# DBoard_Conn.net
KiCad netlist of a schematic drawn in Altium Designer
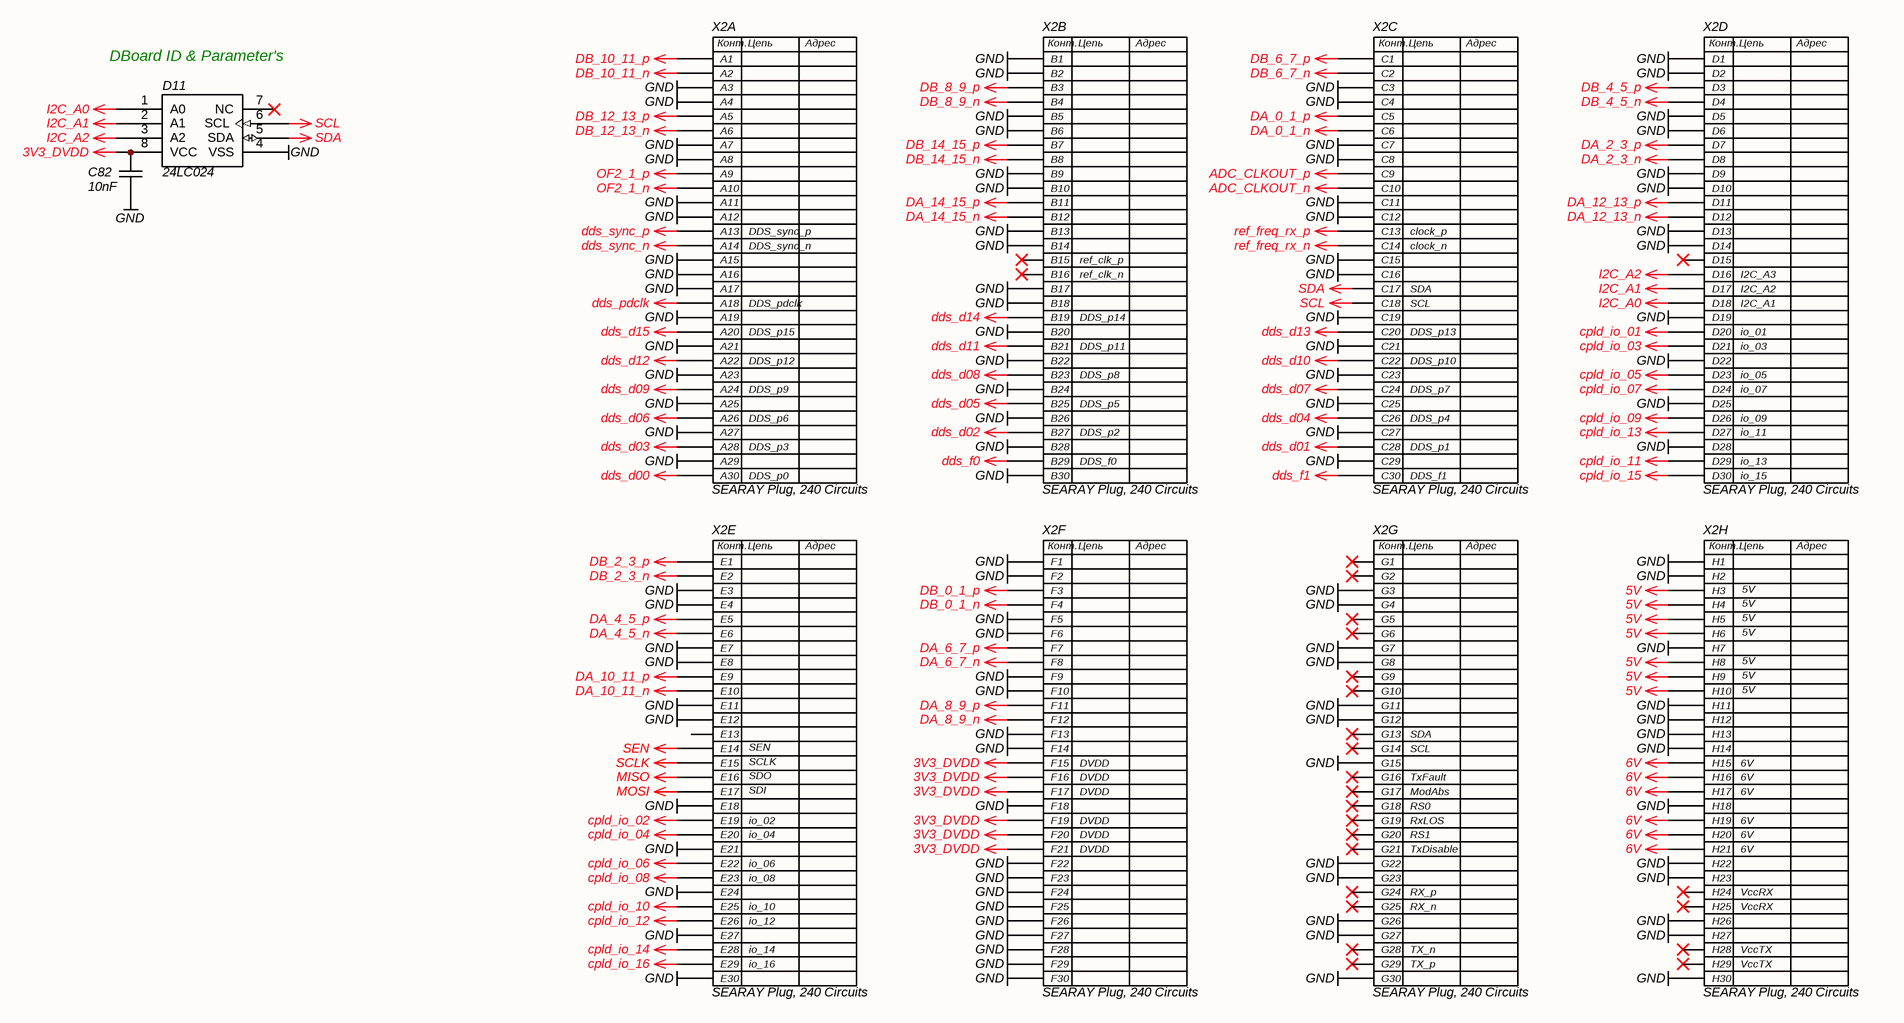
[diagram p0: DBoard_Conn.SchDoc]

(export (version "E")
  (design (tool "Eeschema 10.0.6"))
  (components
    (comp (ref "C82")
      (value "10nF")
      (footprint "C0402")
      (description "SMD Capacitor")
      (fields (field (name "MANUFACTURER") "Murata") (field (name "TOLERANCE") "10%"))
      (libsource (lib "Kintex_SDR") (part "CAP"))
    )
    (comp (ref "D11")
      (value "24LC024")
      (footprint "SOIC_SN8")
      (description "I2C EEPROM")
      (fields (field (name "MANUFACTURER") "Microchip") (field (name "VOLTAGE") "2.5-5.5V"))
      (libsource (lib "Kintex_SDR") (part "24LC024"))
    )
    (comp (ref "X2")
      (value "SEARAY Plug, 240 Circuits")
      (footprint "DBLib:Molex_459703185")
      (description "1.27mm Pitch, SEARAY Plug, 240 Circuits, 2.00mm Unmated Height, 8 Rows, with Pegs")
      (fields (field (name "MANUFACTURER") "Molex"))
      (libsource (lib "") (part "Molex_SEARAY™ 45970_1"))
    )
  )
  (nets
    (net (code "34") (name "3V3_DVDD") (class "Default")
      (node (ref "C82") (pin "2") (pinfunction "2_2") (pintype "passive"))
      (node (ref "D11") (pin "8") (pinfunction "VCC_8") (pintype "power_in"))
      (node (ref "X2") (pin "F15") (pinfunction "F15_F15") (pintype "passive"))
      (node (ref "X2") (pin "F16") (pinfunction "F16_F16") (pintype "passive"))
      (node (ref "X2") (pin "F17") (pinfunction "F17_F17") (pintype "passive"))
      (node (ref "X2") (pin "F19") (pinfunction "F19_F19") (pintype "passive"))
      (node (ref "X2") (pin "F20") (pinfunction "F20_F20") (pintype "passive"))
      (node (ref "X2") (pin "F21") (pinfunction "F21_F21") (pintype "passive"))
    )
    (net (code "35") (name "5V") (class "Default")
      (node (ref "X2") (pin "H10") (pinfunction "H10_H10") (pintype "passive"))
      (node (ref "X2") (pin "H3") (pinfunction "H3_H3") (pintype "passive"))
      (node (ref "X2") (pin "H4") (pinfunction "H4_H4") (pintype "passive"))
      (node (ref "X2") (pin "H5") (pinfunction "H5_H5") (pintype "passive"))
      (node (ref "X2") (pin "H6") (pinfunction "H6_H6") (pintype "passive"))
      (node (ref "X2") (pin "H8") (pinfunction "H8_H8") (pintype "passive"))
      (node (ref "X2") (pin "H9") (pinfunction "H9_H9") (pintype "passive"))
    )
    (net (code "36") (name "6V") (class "Default")
      (node (ref "X2") (pin "H15") (pinfunction "H15_H15") (pintype "passive"))
      (node (ref "X2") (pin "H16") (pinfunction "H16_H16") (pintype "passive"))
      (node (ref "X2") (pin "H17") (pinfunction "H17_H17") (pintype "passive"))
      (node (ref "X2") (pin "H19") (pinfunction "H19_H19") (pintype "passive"))
      (node (ref "X2") (pin "H20") (pinfunction "H20_H20") (pintype "passive"))
      (node (ref "X2") (pin "H21") (pinfunction "H21_H21") (pintype "passive"))
    )
    (net (code "37") (name "ADC_CLKOUT_n") (class "Default")
      (node (ref "X2") (pin "C10") (pinfunction "C10_C10") (pintype "passive"))
    )
    (net (code "38") (name "ADC_CLKOUT_p") (class "Default")
      (node (ref "X2") (pin "C9") (pinfunction "C9_C9") (pintype "passive"))
    )
    (net (code "39") (name "DA_0_1_n") (class "Default")
      (node (ref "X2") (pin "C6") (pinfunction "C6_C6") (pintype "passive"))
    )
    (net (code "40") (name "DA_0_1_p") (class "Default")
      (node (ref "X2") (pin "C5") (pinfunction "C5_C5") (pintype "passive"))
    )
    (net (code "41") (name "DA_2_3_n") (class "Default")
      (node (ref "X2") (pin "D8") (pinfunction "D8_D8") (pintype "passive"))
    )
    (net (code "42") (name "DA_2_3_p") (class "Default")
      (node (ref "X2") (pin "D7") (pinfunction "D7_D7") (pintype "passive"))
    )
    (net (code "43") (name "DA_4_5_n") (class "Default")
      (node (ref "X2") (pin "E6") (pinfunction "E6_E6") (pintype "passive"))
    )
    (net (code "44") (name "DA_4_5_p") (class "Default")
      (node (ref "X2") (pin "E5") (pinfunction "E5_E5") (pintype "passive"))
    )
    (net (code "45") (name "DA_6_7_n") (class "Default")
      (node (ref "X2") (pin "F8") (pinfunction "F8_F8") (pintype "passive"))
    )
    (net (code "46") (name "DA_6_7_p") (class "Default")
      (node (ref "X2") (pin "F7") (pinfunction "F7_F7") (pintype "passive"))
    )
    (net (code "47") (name "DA_8_9_n") (class "Default")
      (node (ref "X2") (pin "F12") (pinfunction "F12_F12") (pintype "passive"))
    )
    (net (code "48") (name "DA_8_9_p") (class "Default")
      (node (ref "X2") (pin "F11") (pinfunction "F11_F11") (pintype "passive"))
    )
    (net (code "49") (name "DA_10_11_n") (class "Default")
      (node (ref "X2") (pin "E10") (pinfunction "E10_E10") (pintype "passive"))
    )
    (net (code "50") (name "DA_10_11_p") (class "Default")
      (node (ref "X2") (pin "E9") (pinfunction "E9_E9") (pintype "passive"))
    )
    (net (code "51") (name "DA_12_13_n") (class "Default")
      (node (ref "X2") (pin "D12") (pinfunction "D12_D12") (pintype "passive"))
    )
    (net (code "52") (name "DA_12_13_p") (class "Default")
      (node (ref "X2") (pin "D11") (pinfunction "D11_D11") (pintype "passive"))
    )
    (net (code "53") (name "DA_14_15_n") (class "Default")
      (node (ref "X2") (pin "B12") (pinfunction "B12_B12") (pintype "passive"))
    )
    (net (code "54") (name "DA_14_15_p") (class "Default")
      (node (ref "X2") (pin "B11") (pinfunction "B11_B11") (pintype "passive"))
    )
    (net (code "55") (name "DB_0_1_n") (class "Default")
      (node (ref "X2") (pin "F4") (pinfunction "F4_F4") (pintype "passive"))
    )
    (net (code "56") (name "DB_0_1_p") (class "Default")
      (node (ref "X2") (pin "F3") (pinfunction "F3_F3") (pintype "passive"))
    )
    (net (code "57") (name "DB_2_3_n") (class "Default")
      (node (ref "X2") (pin "E2") (pinfunction "E2_E2") (pintype "passive"))
    )
    (net (code "58") (name "DB_2_3_p") (class "Default")
      (node (ref "X2") (pin "E1") (pinfunction "E1_E1") (pintype "passive"))
    )
    (net (code "59") (name "DB_4_5_n") (class "Default")
      (node (ref "X2") (pin "D4") (pinfunction "D4_D4") (pintype "passive"))
    )
    (net (code "60") (name "DB_4_5_p") (class "Default")
      (node (ref "X2") (pin "D3") (pinfunction "D3_D3") (pintype "passive"))
    )
    (net (code "61") (name "DB_6_7_n") (class "Default")
      (node (ref "X2") (pin "C2") (pinfunction "C2_C2") (pintype "passive"))
    )
    (net (code "62") (name "DB_6_7_p") (class "Default")
      (node (ref "X2") (pin "C1") (pinfunction "C1_C1") (pintype "passive"))
    )
    (net (code "63") (name "DB_8_9_n") (class "Default")
      (node (ref "X2") (pin "B4") (pinfunction "B4_B4") (pintype "passive"))
    )
    (net (code "64") (name "DB_8_9_p") (class "Default")
      (node (ref "X2") (pin "B3") (pinfunction "B3_B3") (pintype "passive"))
    )
    (net (code "65") (name "DB_10_11_n") (class "Default")
      (node (ref "X2") (pin "A2") (pinfunction "A2_A2") (pintype "passive"))
    )
    (net (code "66") (name "DB_10_11_p") (class "Default")
      (node (ref "X2") (pin "A1") (pinfunction "A1_A1") (pintype "passive"))
    )
    (net (code "67") (name "DB_12_13_n") (class "Default")
      (node (ref "X2") (pin "A6") (pinfunction "A6_A6") (pintype "passive"))
    )
    (net (code "68") (name "DB_12_13_p") (class "Default")
      (node (ref "X2") (pin "A5") (pinfunction "A5_A5") (pintype "passive"))
    )
    (net (code "69") (name "DB_14_15_n") (class "Default")
      (node (ref "X2") (pin "B8") (pinfunction "B8_B8") (pintype "passive"))
    )
    (net (code "70") (name "DB_14_15_p") (class "Default")
      (node (ref "X2") (pin "B7") (pinfunction "B7_B7") (pintype "passive"))
    )
    (net (code "71") (name "GND") (class "Default")
      (node (ref "C82") (pin "1") (pinfunction "1_1") (pintype "passive"))
      (node (ref "D11") (pin "4") (pinfunction "VSS_4") (pintype "power_in"))
      (node (ref "X2") (pin "A11") (pinfunction "A11_A11") (pintype "passive"))
      (node (ref "X2") (pin "A12") (pinfunction "A12_A12") (pintype "passive"))
      (node (ref "X2") (pin "A15") (pinfunction "A15_A15") (pintype "passive"))
      (node (ref "X2") (pin "A16") (pinfunction "A16_A16") (pintype "passive"))
      (node (ref "X2") (pin "A17") (pinfunction "A17_A17") (pintype "passive"))
      (node (ref "X2") (pin "A19") (pinfunction "A19_A19") (pintype "passive"))
      (node (ref "X2") (pin "A21") (pinfunction "A21_A21") (pintype "passive"))
      (node (ref "X2") (pin "A23") (pinfunction "A23_A23") (pintype "passive"))
      (node (ref "X2") (pin "A25") (pinfunction "A25_A25") (pintype "passive"))
      (node (ref "X2") (pin "A27") (pinfunction "A27_A27") (pintype "passive"))
      (node (ref "X2") (pin "A29") (pinfunction "A29_A29") (pintype "passive"))
      (node (ref "X2") (pin "A3") (pinfunction "A3_A3") (pintype "passive"))
      (node (ref "X2") (pin "A4") (pinfunction "A4_A4") (pintype "passive"))
      (node (ref "X2") (pin "A7") (pinfunction "A7_A7") (pintype "passive"))
      (node (ref "X2") (pin "A8") (pinfunction "A8_A8") (pintype "passive"))
      (node (ref "X2") (pin "B1") (pinfunction "B1_B1") (pintype "passive"))
      (node (ref "X2") (pin "B10") (pinfunction "B10_B10") (pintype "passive"))
      (node (ref "X2") (pin "B13") (pinfunction "B13_B13") (pintype "passive"))
      (node (ref "X2") (pin "B14") (pinfunction "B14_B14") (pintype "passive"))
      (node (ref "X2") (pin "B17") (pinfunction "B17_B17") (pintype "passive"))
      (node (ref "X2") (pin "B18") (pinfunction "B18_B18") (pintype "passive"))
      (node (ref "X2") (pin "B2") (pinfunction "B2_B2") (pintype "passive"))
      (node (ref "X2") (pin "B20") (pinfunction "B20_B20") (pintype "passive"))
      (node (ref "X2") (pin "B22") (pinfunction "B22_B22") (pintype "passive"))
      (node (ref "X2") (pin "B24") (pinfunction "B24_B24") (pintype "passive"))
      (node (ref "X2") (pin "B26") (pinfunction "B26_B26") (pintype "passive"))
      (node (ref "X2") (pin "B28") (pinfunction "B28_B28") (pintype "passive"))
      (node (ref "X2") (pin "B30") (pinfunction "B30_B30") (pintype "passive"))
      (node (ref "X2") (pin "B5") (pinfunction "B5_B5") (pintype "passive"))
      (node (ref "X2") (pin "B6") (pinfunction "B6_B6") (pintype "passive"))
      (node (ref "X2") (pin "B9") (pinfunction "B9_B9") (pintype "passive"))
      (node (ref "X2") (pin "C11") (pinfunction "C11_C11") (pintype "passive"))
      (node (ref "X2") (pin "C12") (pinfunction "C12_C12") (pintype "passive"))
      (node (ref "X2") (pin "C15") (pinfunction "C15_C15") (pintype "passive"))
      (node (ref "X2") (pin "C16") (pinfunction "C16_C16") (pintype "passive"))
      (node (ref "X2") (pin "C19") (pinfunction "C19_C19") (pintype "passive"))
      (node (ref "X2") (pin "C21") (pinfunction "C21_C21") (pintype "passive"))
      (node (ref "X2") (pin "C23") (pinfunction "C23_C23") (pintype "passive"))
      (node (ref "X2") (pin "C25") (pinfunction "C25_C25") (pintype "passive"))
      (node (ref "X2") (pin "C27") (pinfunction "C27_C27") (pintype "passive"))
      (node (ref "X2") (pin "C29") (pinfunction "C29_C29") (pintype "passive"))
      (node (ref "X2") (pin "C3") (pinfunction "C3_C3") (pintype "passive"))
      (node (ref "X2") (pin "C4") (pinfunction "C4_C4") (pintype "passive"))
      (node (ref "X2") (pin "C7") (pinfunction "C7_C7") (pintype "passive"))
      (node (ref "X2") (pin "C8") (pinfunction "C8_C8") (pintype "passive"))
      (node (ref "X2") (pin "D1") (pinfunction "D1_D1") (pintype "passive"))
      (node (ref "X2") (pin "D10") (pinfunction "D10_D10") (pintype "passive"))
      (node (ref "X2") (pin "D13") (pinfunction "D13_D13") (pintype "passive"))
      (node (ref "X2") (pin "D14") (pinfunction "D14_D14") (pintype "passive"))
      (node (ref "X2") (pin "D19") (pinfunction "D19_D19") (pintype "passive"))
      (node (ref "X2") (pin "D2") (pinfunction "D2_D2") (pintype "passive"))
      (node (ref "X2") (pin "D22") (pinfunction "D22_D22") (pintype "passive"))
      (node (ref "X2") (pin "D25") (pinfunction "D25_D25") (pintype "passive"))
      (node (ref "X2") (pin "D28") (pinfunction "D28_D28") (pintype "passive"))
      (node (ref "X2") (pin "D5") (pinfunction "D5_D5") (pintype "passive"))
      (node (ref "X2") (pin "D6") (pinfunction "D6_D6") (pintype "passive"))
      (node (ref "X2") (pin "D9") (pinfunction "D9_D9") (pintype "passive"))
      (node (ref "X2") (pin "E11") (pinfunction "E11_E11") (pintype "passive"))
      (node (ref "X2") (pin "E12") (pinfunction "E12_E12") (pintype "passive"))
      (node (ref "X2") (pin "E18") (pinfunction "E18_E18") (pintype "passive"))
      (node (ref "X2") (pin "E21") (pinfunction "E21_E21") (pintype "passive"))
      (node (ref "X2") (pin "E24") (pinfunction "E24_E24") (pintype "passive"))
      (node (ref "X2") (pin "E27") (pinfunction "E27_E27") (pintype "passive"))
      (node (ref "X2") (pin "E3") (pinfunction "E3_E3") (pintype "passive"))
      (node (ref "X2") (pin "E30") (pinfunction "E30_E30") (pintype "passive"))
      (node (ref "X2") (pin "E4") (pinfunction "E4_E4") (pintype "passive"))
      (node (ref "X2") (pin "E7") (pinfunction "E7_E7") (pintype "passive"))
      (node (ref "X2") (pin "E8") (pinfunction "E8_E8") (pintype "passive"))
      (node (ref "X2") (pin "F1") (pinfunction "F1_F1") (pintype "passive"))
      (node (ref "X2") (pin "F10") (pinfunction "F10_F10") (pintype "passive"))
      (node (ref "X2") (pin "F13") (pinfunction "F13_F13") (pintype "passive"))
      (node (ref "X2") (pin "F14") (pinfunction "F14_F14") (pintype "passive"))
      (node (ref "X2") (pin "F18") (pinfunction "F18_F18") (pintype "passive"))
      (node (ref "X2") (pin "F2") (pinfunction "F2_F2") (pintype "passive"))
      (node (ref "X2") (pin "F22") (pinfunction "F22_F22") (pintype "passive"))
      (node (ref "X2") (pin "F23") (pinfunction "F23_F23") (pintype "passive"))
      (node (ref "X2") (pin "F24") (pinfunction "F24_F24") (pintype "passive"))
      (node (ref "X2") (pin "F25") (pinfunction "F25_F25") (pintype "passive"))
      (node (ref "X2") (pin "F26") (pinfunction "F26_F26") (pintype "passive"))
      (node (ref "X2") (pin "F27") (pinfunction "F27_F27") (pintype "passive"))
      (node (ref "X2") (pin "F28") (pinfunction "F28_F28") (pintype "passive"))
      (node (ref "X2") (pin "F29") (pinfunction "F29_F29") (pintype "passive"))
      (node (ref "X2") (pin "F30") (pinfunction "F30_F30") (pintype "passive"))
      (node (ref "X2") (pin "F5") (pinfunction "F5_F5") (pintype "passive"))
      (node (ref "X2") (pin "F6") (pinfunction "F6_F6") (pintype "passive"))
      (node (ref "X2") (pin "F9") (pinfunction "F9_F9") (pintype "passive"))
      (node (ref "X2") (pin "G11") (pinfunction "G11_G11") (pintype "passive"))
      (node (ref "X2") (pin "G12") (pinfunction "G12_G12") (pintype "passive"))
      (node (ref "X2") (pin "G15") (pinfunction "G15_G15") (pintype "passive"))
      (node (ref "X2") (pin "G22") (pinfunction "G22_G22") (pintype "passive"))
      (node (ref "X2") (pin "G23") (pinfunction "G23_G23") (pintype "passive"))
      (node (ref "X2") (pin "G26") (pinfunction "G26_G26") (pintype "passive"))
      (node (ref "X2") (pin "G27") (pinfunction "G27_G27") (pintype "passive"))
      (node (ref "X2") (pin "G3") (pinfunction "G3_G3") (pintype "passive"))
      (node (ref "X2") (pin "G30") (pinfunction "G30_G30") (pintype "passive"))
      (node (ref "X2") (pin "G4") (pinfunction "G4_G4") (pintype "passive"))
      (node (ref "X2") (pin "G7") (pinfunction "G7_G7") (pintype "passive"))
      (node (ref "X2") (pin "G8") (pinfunction "G8_G8") (pintype "passive"))
      (node (ref "X2") (pin "H1") (pinfunction "H1_H1") (pintype "passive"))
      (node (ref "X2") (pin "H11") (pinfunction "H11_H11") (pintype "passive"))
      (node (ref "X2") (pin "H12") (pinfunction "H12_H12") (pintype "passive"))
      (node (ref "X2") (pin "H13") (pinfunction "H13_H13") (pintype "passive"))
      (node (ref "X2") (pin "H14") (pinfunction "H14_H14") (pintype "passive"))
      (node (ref "X2") (pin "H18") (pinfunction "H18_H18") (pintype "passive"))
      (node (ref "X2") (pin "H2") (pinfunction "H2_H2") (pintype "passive"))
      (node (ref "X2") (pin "H22") (pinfunction "H22_H22") (pintype "passive"))
      (node (ref "X2") (pin "H23") (pinfunction "H23_H23") (pintype "passive"))
      (node (ref "X2") (pin "H26") (pinfunction "H26_H26") (pintype "passive"))
      (node (ref "X2") (pin "H27") (pinfunction "H27_H27") (pintype "passive"))
      (node (ref "X2") (pin "H30") (pinfunction "H30_H30") (pintype "passive"))
      (node (ref "X2") (pin "H7") (pinfunction "H7_H7") (pintype "passive"))
    )
    (net (code "72") (name "I2C_A0") (class "Default")
      (node (ref "D11") (pin "1") (pinfunction "A0_1") (pintype "passive"))
      (node (ref "X2") (pin "D18") (pinfunction "D18_D18") (pintype "passive"))
    )
    (net (code "73") (name "I2C_A1") (class "Default")
      (node (ref "D11") (pin "2") (pinfunction "A1_2") (pintype "passive"))
      (node (ref "X2") (pin "D17") (pinfunction "D17_D17") (pintype "passive"))
    )
    (net (code "74") (name "I2C_A2") (class "Default")
      (node (ref "D11") (pin "3") (pinfunction "A2_3") (pintype "passive"))
      (node (ref "X2") (pin "D16") (pinfunction "D16_D16") (pintype "passive"))
    )
    (net (code "75") (name "MISO") (class "Default")
      (node (ref "X2") (pin "E16") (pinfunction "E16_E16") (pintype "passive"))
    )
    (net (code "76") (name "MOSI") (class "Default")
      (node (ref "X2") (pin "E17") (pinfunction "E17_E17") (pintype "passive"))
    )
    (net (code "77") (name "OF2_1_n") (class "Default")
      (node (ref "X2") (pin "A10") (pinfunction "A10_A10") (pintype "passive"))
    )
    (net (code "78") (name "OF2_1_p") (class "Default")
      (node (ref "X2") (pin "A9") (pinfunction "A9_A9") (pintype "passive"))
    )
    (net (code "79") (name "SCL") (class "Default")
      (node (ref "D11") (pin "6") (pinfunction "SCL_6") (pintype "input"))
      (node (ref "X2") (pin "C18") (pinfunction "C18_C18") (pintype "passive"))
    )
    (net (code "80") (name "SCLK") (class "Default")
      (node (ref "X2") (pin "E15") (pinfunction "E15_E15") (pintype "passive"))
    )
    (net (code "81") (name "SDA") (class "Default")
      (node (ref "D11") (pin "5") (pinfunction "SDA_5") (pintype "bidirectional"))
      (node (ref "X2") (pin "C17") (pinfunction "C17_C17") (pintype "passive"))
    )
    (net (code "82") (name "SEN") (class "Default")
      (node (ref "X2") (pin "E14") (pinfunction "E14_E14") (pintype "passive"))
    )
    (net (code "83") (name "cpld_io_01") (class "Default")
      (node (ref "X2") (pin "D20") (pinfunction "D20_D20") (pintype "passive"))
    )
    (net (code "84") (name "cpld_io_02") (class "Default")
      (node (ref "X2") (pin "E19") (pinfunction "E19_E19") (pintype "passive"))
    )
    (net (code "85") (name "cpld_io_03") (class "Default")
      (node (ref "X2") (pin "D21") (pinfunction "D21_D21") (pintype "passive"))
    )
    (net (code "86") (name "cpld_io_04") (class "Default")
      (node (ref "X2") (pin "E20") (pinfunction "E20_E20") (pintype "passive"))
    )
    (net (code "87") (name "cpld_io_05") (class "Default")
      (node (ref "X2") (pin "D23") (pinfunction "D23_D23") (pintype "passive"))
    )
    (net (code "88") (name "cpld_io_06") (class "Default")
      (node (ref "X2") (pin "E22") (pinfunction "E22_E22") (pintype "passive"))
    )
    (net (code "89") (name "cpld_io_07") (class "Default")
      (node (ref "X2") (pin "D24") (pinfunction "D24_D24") (pintype "passive"))
    )
    (net (code "90") (name "cpld_io_08") (class "Default")
      (node (ref "X2") (pin "E23") (pinfunction "E23_E23") (pintype "passive"))
    )
    (net (code "91") (name "cpld_io_09") (class "Default")
      (node (ref "X2") (pin "D26") (pinfunction "D26_D26") (pintype "passive"))
    )
    (net (code "92") (name "cpld_io_10") (class "Default")
      (node (ref "X2") (pin "E25") (pinfunction "E25_E25") (pintype "passive"))
    )
    (net (code "93") (name "cpld_io_11") (class "Default")
      (node (ref "X2") (pin "D29") (pinfunction "D29_D29") (pintype "passive"))
    )
    (net (code "94") (name "cpld_io_12") (class "Default")
      (node (ref "X2") (pin "E26") (pinfunction "E26_E26") (pintype "passive"))
    )
    (net (code "95") (name "cpld_io_13") (class "Default")
      (node (ref "X2") (pin "D27") (pinfunction "D27_D27") (pintype "passive"))
    )
    (net (code "96") (name "cpld_io_14") (class "Default")
      (node (ref "X2") (pin "E28") (pinfunction "E28_E28") (pintype "passive"))
    )
    (net (code "97") (name "cpld_io_15") (class "Default")
      (node (ref "X2") (pin "D30") (pinfunction "D30_D30") (pintype "passive"))
    )
    (net (code "98") (name "cpld_io_16") (class "Default")
      (node (ref "X2") (pin "E29") (pinfunction "E29_E29") (pintype "passive"))
    )
    (net (code "99") (name "dds_d00") (class "Default")
      (node (ref "X2") (pin "A30") (pinfunction "A30_A30") (pintype "passive"))
    )
    (net (code "100") (name "dds_d01") (class "Default")
      (node (ref "X2") (pin "C28") (pinfunction "C28_C28") (pintype "passive"))
    )
    (net (code "101") (name "dds_d02") (class "Default")
      (node (ref "X2") (pin "B27") (pinfunction "B27_B27") (pintype "passive"))
    )
    (net (code "102") (name "dds_d03") (class "Default")
      (node (ref "X2") (pin "A28") (pinfunction "A28_A28") (pintype "passive"))
    )
    (net (code "103") (name "dds_d04") (class "Default")
      (node (ref "X2") (pin "C26") (pinfunction "C26_C26") (pintype "passive"))
    )
    (net (code "104") (name "dds_d05") (class "Default")
      (node (ref "X2") (pin "B25") (pinfunction "B25_B25") (pintype "passive"))
    )
    (net (code "105") (name "dds_d06") (class "Default")
      (node (ref "X2") (pin "A26") (pinfunction "A26_A26") (pintype "passive"))
    )
    (net (code "106") (name "dds_d07") (class "Default")
      (node (ref "X2") (pin "C24") (pinfunction "C24_C24") (pintype "passive"))
    )
    (net (code "107") (name "dds_d08") (class "Default")
      (node (ref "X2") (pin "B23") (pinfunction "B23_B23") (pintype "passive"))
    )
    (net (code "108") (name "dds_d09") (class "Default")
      (node (ref "X2") (pin "A24") (pinfunction "A24_A24") (pintype "passive"))
    )
    (net (code "109") (name "dds_d10") (class "Default")
      (node (ref "X2") (pin "C22") (pinfunction "C22_C22") (pintype "passive"))
    )
    (net (code "110") (name "dds_d11") (class "Default")
      (node (ref "X2") (pin "B21") (pinfunction "B21_B21") (pintype "passive"))
    )
    (net (code "111") (name "dds_d12") (class "Default")
      (node (ref "X2") (pin "A22") (pinfunction "A22_A22") (pintype "passive"))
    )
    (net (code "112") (name "dds_d13") (class "Default")
      (node (ref "X2") (pin "C20") (pinfunction "C20_C20") (pintype "passive"))
    )
    (net (code "113") (name "dds_d14") (class "Default")
      (node (ref "X2") (pin "B19") (pinfunction "B19_B19") (pintype "passive"))
    )
    (net (code "114") (name "dds_d15") (class "Default")
      (node (ref "X2") (pin "A20") (pinfunction "A20_A20") (pintype "passive"))
    )
    (net (code "115") (name "dds_f0") (class "Default")
      (node (ref "X2") (pin "B29") (pinfunction "B29_B29") (pintype "passive"))
    )
    (net (code "116") (name "dds_f1") (class "Default")
      (node (ref "X2") (pin "C30") (pinfunction "C30_C30") (pintype "passive"))
    )
    (net (code "117") (name "dds_pdclk") (class "Default")
      (node (ref "X2") (pin "A18") (pinfunction "A18_A18") (pintype "passive"))
    )
    (net (code "118") (name "dds_sync_n") (class "Default")
      (node (ref "X2") (pin "A14") (pinfunction "A14_A14") (pintype "passive"))
    )
    (net (code "119") (name "dds_sync_p") (class "Default")
      (node (ref "X2") (pin "A13") (pinfunction "A13_A13") (pintype "passive"))
    )
    (net (code "120") (name "ref_freq_rx_n") (class "Default")
      (node (ref "X2") (pin "C14") (pinfunction "C14_C14") (pintype "passive"))
    )
    (net (code "121") (name "ref_freq_rx_p") (class "Default")
      (node (ref "X2") (pin "C13") (pinfunction "C13_C13") (pintype "passive"))
    )
    (net (code "122") (name "unconnected-(D11-NC-Pad7)") (class "Default")
      (node (ref "D11") (pin "7") (pinfunction "NC_7") (pintype "passive+no_connect"))
    )
    (net (code "123") (name "unconnected-(X2-PadB15)") (class "Default")
      (node (ref "X2") (pin "B15") (pinfunction "B15_B15") (pintype "passive+no_connect"))
    )
    (net (code "124") (name "unconnected-(X2-PadB16)") (class "Default")
      (node (ref "X2") (pin "B16") (pinfunction "B16_B16") (pintype "passive+no_connect"))
    )
    (net (code "125") (name "unconnected-(X2-PadD15)") (class "Default")
      (node (ref "X2") (pin "D15") (pinfunction "D15_D15") (pintype "passive+no_connect"))
    )
    (net (code "126") (name "unconnected-(X2-PadE13)") (class "Default")
      (node (ref "X2") (pin "E13") (pinfunction "E13_E13") (pintype "passive"))
    )
    (net (code "127") (name "unconnected-(X2-PadG1)") (class "Default")
      (node (ref "X2") (pin "G1") (pinfunction "G1_G1") (pintype "passive+no_connect"))
    )
    (net (code "128") (name "unconnected-(X2-PadG2)") (class "Default")
      (node (ref "X2") (pin "G2") (pinfunction "G2_G2") (pintype "passive+no_connect"))
    )
    (net (code "129") (name "unconnected-(X2-PadG5)") (class "Default")
      (node (ref "X2") (pin "G5") (pinfunction "G5_G5") (pintype "passive+no_connect"))
    )
    (net (code "130") (name "unconnected-(X2-PadG6)") (class "Default")
      (node (ref "X2") (pin "G6") (pinfunction "G6_G6") (pintype "passive+no_connect"))
    )
    (net (code "131") (name "unconnected-(X2-PadG9)") (class "Default")
      (node (ref "X2") (pin "G9") (pinfunction "G9_G9") (pintype "passive+no_connect"))
    )
    (net (code "132") (name "unconnected-(X2-PadG10)") (class "Default")
      (node (ref "X2") (pin "G10") (pinfunction "G10_G10") (pintype "passive+no_connect"))
    )
    (net (code "133") (name "unconnected-(X2-PadG13)") (class "Default")
      (node (ref "X2") (pin "G13") (pinfunction "G13_G13") (pintype "passive+no_connect"))
    )
    (net (code "134") (name "unconnected-(X2-PadG14)") (class "Default")
      (node (ref "X2") (pin "G14") (pinfunction "G14_G14") (pintype "passive+no_connect"))
    )
    (net (code "135") (name "unconnected-(X2-PadG16)") (class "Default")
      (node (ref "X2") (pin "G16") (pinfunction "G16_G16") (pintype "passive+no_connect"))
    )
    (net (code "136") (name "unconnected-(X2-PadG17)") (class "Default")
      (node (ref "X2") (pin "G17") (pinfunction "G17_G17") (pintype "passive+no_connect"))
    )
    (net (code "137") (name "unconnected-(X2-PadG18)") (class "Default")
      (node (ref "X2") (pin "G18") (pinfunction "G18_G18") (pintype "passive+no_connect"))
    )
    (net (code "138") (name "unconnected-(X2-PadG19)") (class "Default")
      (node (ref "X2") (pin "G19") (pinfunction "G19_G19") (pintype "passive+no_connect"))
    )
    (net (code "139") (name "unconnected-(X2-PadG20)") (class "Default")
      (node (ref "X2") (pin "G20") (pinfunction "G20_G20") (pintype "passive+no_connect"))
    )
    (net (code "140") (name "unconnected-(X2-PadG21)") (class "Default")
      (node (ref "X2") (pin "G21") (pinfunction "G21_G21") (pintype "passive+no_connect"))
    )
    (net (code "141") (name "unconnected-(X2-PadG24)") (class "Default")
      (node (ref "X2") (pin "G24") (pinfunction "G24_G24") (pintype "passive+no_connect"))
    )
    (net (code "142") (name "unconnected-(X2-PadG25)") (class "Default")
      (node (ref "X2") (pin "G25") (pinfunction "G25_G25") (pintype "passive+no_connect"))
    )
    (net (code "143") (name "unconnected-(X2-PadG28)") (class "Default")
      (node (ref "X2") (pin "G28") (pinfunction "G28_G28") (pintype "passive+no_connect"))
    )
    (net (code "144") (name "unconnected-(X2-PadG29)") (class "Default")
      (node (ref "X2") (pin "G29") (pinfunction "G29_G29") (pintype "passive+no_connect"))
    )
    (net (code "145") (name "unconnected-(X2-PadH24)") (class "Default")
      (node (ref "X2") (pin "H24") (pinfunction "H24_H24") (pintype "passive+no_connect"))
    )
    (net (code "146") (name "unconnected-(X2-PadH25)") (class "Default")
      (node (ref "X2") (pin "H25") (pinfunction "H25_H25") (pintype "passive+no_connect"))
    )
    (net (code "147") (name "unconnected-(X2-PadH28)") (class "Default")
      (node (ref "X2") (pin "H28") (pinfunction "H28_H28") (pintype "passive+no_connect"))
    )
    (net (code "148") (name "unconnected-(X2-PadH29)") (class "Default")
      (node (ref "X2") (pin "H29") (pinfunction "H29_H29") (pintype "passive+no_connect"))
    )
  )
)
